# Sch_Dr_LD.net
KiCad netlist of a schematic drawn in Altium Designer
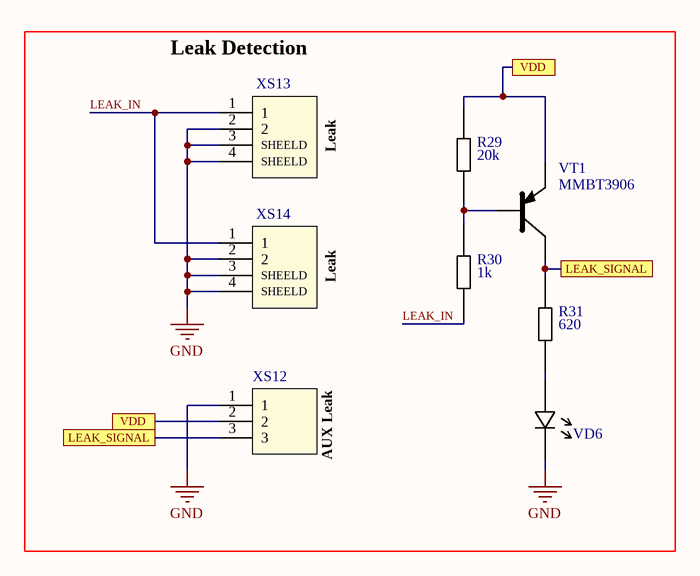
[diagram p0: Sch_Dr_LD .SchDoc]

(export (version "E")
  (design (tool "Eeschema 10.0.6"))
  (components
    (comp (ref "R29")
      (value "20k")
      (footprint "Res_0603")
      (description "CR-03FL7---20K")
      (libsource (lib "Dr_lib") (part "Res_"))
    )
    (comp (ref "R30")
      (value "1k")
      (footprint "Res_0603")
      (description "CR-03FL7----1K")
      (libsource (lib "Dr_lib") (part "Res_"))
    )
    (comp (ref "R31")
      (value "620")
      (footprint "Res_0603")
      (description "CR-03FL7--620R")
      (libsource (lib "Dr_lib") (part "Res_"))
    )
    (comp (ref "VD6")
      (value "TO-1608BC-PG")
      (footprint "0603_LED")
      (description "SMD LED Green")
      (libsource (lib "Dr_lib") (part "LED_"))
    )
    (comp (ref "VT1")
      (value "MMBT3906")
      (footprint "SOT-23-3")
      (description "SOT-23, 40V, 0.2A, NPN Bipolar Transistor")
      (libsource (lib "Dr_lib") (part "MMBT3906"))
    )
    (comp (ref "XS12") (value "PLS-3") (footprint "3X") (libsource (lib "Dr_lib") (part "PLS-3")))
    (comp (ref "XS13")
      (value "BM02B-GHS-TBT(LF)(SN)(N)")
      (footprint "BM02B-GHS-TBT")
      (libsource (lib "Dr_lib") (part "BM02B-GHS-TBT(LF)(SN)(N)"))
    )
    (comp (ref "XS14")
      (value "BM02B-GHS-TBT(LF)(SN)(N)")
      (footprint "BM02B-GHS-TBT")
      (libsource (lib "Dr_lib") (part "BM02B-GHS-TBT(LF)(SN)(N)"))
    )
  )
  (nets
    (net (code "1") (name "/LEAK_IN") (class "Default")
      (node (ref "R30") (pin "2") (pinfunction "2_2") (pintype "passive"))
      (node (ref "XS13") (pin "1") (pinfunction "1_1") (pintype "passive"))
      (node (ref "XS14") (pin "1") (pinfunction "1_1") (pintype "passive"))
    )
    (net (code "2") (name "/LEAK_SIGNAL") (class "Default")
      (node (ref "R31") (pin "1") (pinfunction "1_1") (pintype "passive"))
      (node (ref "VT1") (pin "3") (pinfunction "C_3") (pintype "passive"))
      (node (ref "XS12") (pin "3") (pinfunction "3_3") (pintype "passive"))
    )
    (net (code "3") (name "/VDD") (class "Default")
      (node (ref "R29") (pin "1") (pinfunction "1_1") (pintype "passive"))
      (node (ref "VT1") (pin "2") (pinfunction "E_2") (pintype "passive"))
      (node (ref "XS12") (pin "2") (pinfunction "2_2") (pintype "passive"))
    )
    (net (code "4") (name "GND") (class "Default")
      (node (ref "VD6") (pin "1") (pinfunction "K_1") (pintype "passive"))
      (node (ref "XS12") (pin "1") (pinfunction "1_1") (pintype "passive"))
      (node (ref "XS13") (pin "2") (pinfunction "2_2") (pintype "passive"))
      (node (ref "XS13") (pin "3") (pinfunction "SHEELD_3") (pintype "passive"))
      (node (ref "XS13") (pin "4") (pinfunction "SHEELD_4") (pintype "passive"))
      (node (ref "XS14") (pin "2") (pinfunction "2_2") (pintype "passive"))
      (node (ref "XS14") (pin "3") (pinfunction "SHEELD_3") (pintype "passive"))
      (node (ref "XS14") (pin "4") (pinfunction "SHEELD_4") (pintype "passive"))
    )
    (net (code "5") (name "Net-(VD6-A)") (class "Default")
      (node (ref "R31") (pin "2") (pinfunction "2_2") (pintype "passive"))
      (node (ref "VD6") (pin "2") (pinfunction "A_2") (pintype "passive"))
    )
    (net (code "6") (name "Net-(VT1-B)") (class "Default")
      (node (ref "R29") (pin "2") (pinfunction "2_2") (pintype "passive"))
      (node (ref "R30") (pin "1") (pinfunction "1_1") (pintype "passive"))
      (node (ref "VT1") (pin "1") (pinfunction "B_1") (pintype "passive"))
    )
  )
)
